# topboard-v2_0.net
KiCad netlist of a schematic drawn in EAGLE
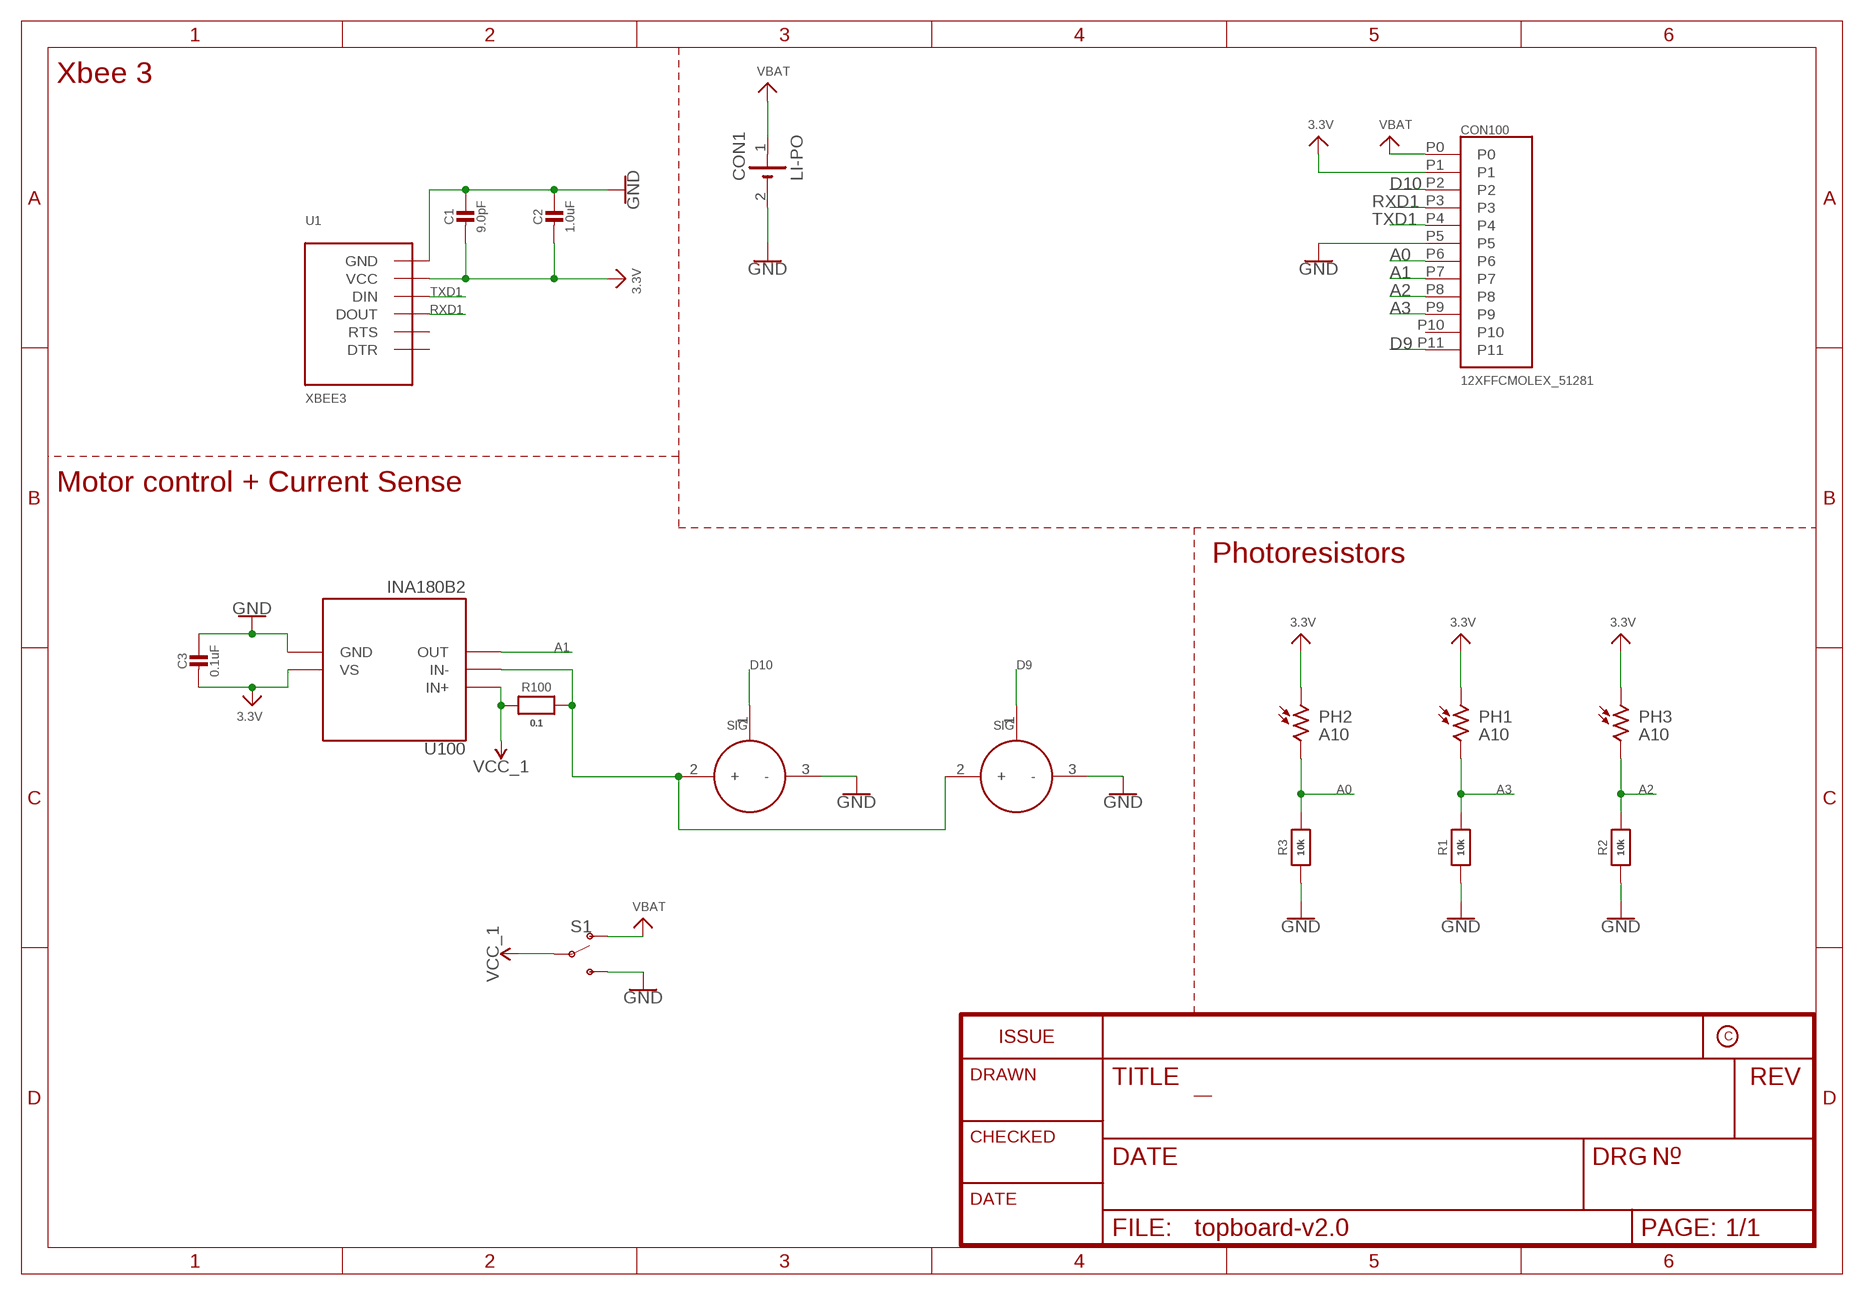
[diagram p0: schematic, sheet 1]

(export (version "E")
  (design (tool "Eeschema 10.0.6"))
  (components
    (comp (ref "C1")
      (value "9.0pF")
      (footprint "eagle-import:_0603MP")
      (libsource (lib "eagle-import") (part "CAP_CERAMIC_0603MP"))
    )
    (comp (ref "C2")
      (value "1.0uF")
      (footprint "eagle-import:_0603MP")
      (libsource (lib "eagle-import") (part "CAP_CERAMIC_0603MP"))
    )
    (comp (ref "C3")
      (value "0.1uF")
      (footprint "eagle-import:_0603MP")
      (libsource (lib "eagle-import") (part "CAP_CERAMIC_0603MP"))
    )
    (comp (ref "CON1")
      (value "LI-PO")
      (footprint "eagle-import:1X02_BATT")
      (libsource (lib "eagle-import") (part "LI-PO"))
    )
    (comp (ref "CON100")
      (value "12XFFCMOLEX_51281")
      (footprint "eagle-import:MOLEX_51281-1294")
      (libsource (lib "eagle-import") (part "12XFFCMOLEX_51281"))
    )
    (comp (ref "M1")
      (value "SERVO")
      (footprint "eagle-import:1X03_SERVO")
      (libsource (lib "eagle-import") (part "SERVO"))
    )
    (comp (ref "M2")
      (value "SERVO")
      (footprint "eagle-import:1X03_SERVO")
      (libsource (lib "eagle-import") (part "SERVO"))
    )
    (comp (ref "PH1")
      (value "A10")
      (footprint "eagle-import:PHOTORESISTOR")
      (libsource (lib "eagle-import") (part "A10"))
    )
    (comp (ref "PH2")
      (value "A10")
      (footprint "eagle-import:PHOTORESISTOR")
      (libsource (lib "eagle-import") (part "A10"))
    )
    (comp (ref "PH3")
      (value "A10")
      (footprint "eagle-import:PHOTORESISTOR")
      (libsource (lib "eagle-import") (part "A10"))
    )
    (comp (ref "R1")
      (value "10k")
      (footprint "eagle-import:_0603MP")
      (libsource (lib "eagle-import") (part "RESISTOR_0603MP"))
    )
    (comp (ref "R2")
      (value "10k")
      (footprint "eagle-import:_0603MP")
      (libsource (lib "eagle-import") (part "RESISTOR_0603MP"))
    )
    (comp (ref "R3")
      (value "10k")
      (footprint "eagle-import:_0603MP")
      (libsource (lib "eagle-import") (part "RESISTOR_0603MP"))
    )
    (comp (ref "R100")
      (value "0.1")
      (footprint "eagle-import:_0603MP")
      (libsource (lib "eagle-import") (part "RESISTOR_0603MP"))
    )
    (comp (ref "S1")
      (value "SWITCH-SPDT-SMD-RIGHT-ANGLE")
      (footprint "eagle-import:SWITCH_SPST_SMD_A")
      (libsource (lib "eagle-import") (part "SWITCH-SPDT-SMD-RIGHT-ANGLE"))
    )
    (comp (ref "U1")
      (value "XBEE3")
      (footprint "eagle-import:XBEE3_MICRO")
      (libsource (lib "eagle-import") (part "XBEE3"))
    )
    (comp (ref "U100")
      (value "INA180B2")
      (footprint "eagle-import:SOT23-5")
      (libsource (lib "eagle-import") (part "INA180B2"))
    )
  )
  (nets
    (net (code "1") (name "/A0") (class "Default")
      (node (ref "CON100") (pin "P6") (pinfunction "P6_P6") (pintype "bidirectional"))
      (node (ref "PH2") (pin "2") (pinfunction "2_2") (pintype "passive"))
      (node (ref "R3") (pin "2") (pinfunction "2_2") (pintype "passive"))
    )
    (net (code "2") (name "/A1") (class "Default")
      (node (ref "CON100") (pin "P7") (pinfunction "P7_P7") (pintype "bidirectional"))
      (node (ref "U100") (pin "4") (pinfunction "OUT_4") (pintype "bidirectional"))
    )
    (net (code "3") (name "/A2") (class "Default")
      (node (ref "CON100") (pin "P8") (pinfunction "P8_P8") (pintype "bidirectional"))
      (node (ref "PH3") (pin "2") (pinfunction "2_2") (pintype "passive"))
      (node (ref "R2") (pin "2") (pinfunction "2_2") (pintype "passive"))
    )
    (net (code "4") (name "/A3") (class "Default")
      (node (ref "CON100") (pin "P9") (pinfunction "P9_P9") (pintype "bidirectional"))
      (node (ref "PH1") (pin "2") (pinfunction "2_2") (pintype "passive"))
      (node (ref "R1") (pin "2") (pinfunction "2_2") (pintype "passive"))
    )
    (net (code "5") (name "/D9") (class "Default")
      (node (ref "CON100") (pin "P11") (pinfunction "P11_P11") (pintype "bidirectional"))
      (node (ref "M1") (pin "1") (pinfunction "SIG_1") (pintype "bidirectional"))
    )
    (net (code "6") (name "/D10") (class "Default")
      (node (ref "CON100") (pin "P2") (pinfunction "P2_P2") (pintype "bidirectional"))
      (node (ref "M2") (pin "1") (pinfunction "SIG_1") (pintype "bidirectional"))
    )
    (net (code "7") (name "/RXD1") (class "Default")
      (node (ref "CON100") (pin "P3") (pinfunction "P3_P3") (pintype "bidirectional"))
      (node (ref "U1") (pin "DOUT/DIO13") (pinfunction "DOUT_DOUT/DIO13") (pintype "bidirectional"))
    )
    (net (code "8") (name "/TXD1") (class "Default")
      (node (ref "CON100") (pin "P4") (pinfunction "P4_P4") (pintype "bidirectional"))
      (node (ref "U1") (pin "DIN/CONFIG/DIO14") (pinfunction "DIN_DIN/CONFIG/DIO14") (pintype "bidirectional"))
    )
    (net (code "9") (name "3.3V") (class "Default")
      (node (ref "C1") (pin "2") (pinfunction "2_2") (pintype "passive"))
      (node (ref "C2") (pin "2") (pinfunction "2_2") (pintype "passive"))
      (node (ref "C3") (pin "2") (pinfunction "2_2") (pintype "passive"))
      (node (ref "CON100") (pin "P1") (pinfunction "P1_P1") (pintype "bidirectional"))
      (node (ref "PH1") (pin "1") (pinfunction "1_1") (pintype "passive"))
      (node (ref "PH2") (pin "1") (pinfunction "1_1") (pintype "passive"))
      (node (ref "PH3") (pin "1") (pinfunction "1_1") (pintype "passive"))
      (node (ref "U1") (pin "VCC") (pinfunction "VCC_VCC") (pintype "bidirectional"))
      (node (ref "U100") (pin "5") (pinfunction "VS_5") (pintype "bidirectional"))
    )
    (net (code "10") (name "GND") (class "Default")
      (node (ref "C1") (pin "1") (pinfunction "1_1") (pintype "passive"))
      (node (ref "C2") (pin "1") (pinfunction "1_1") (pintype "passive"))
      (node (ref "C3") (pin "1") (pinfunction "1_1") (pintype "passive"))
      (node (ref "CON1") (pin "2") (pinfunction "-_2") (pintype "passive"))
      (node (ref "CON100") (pin "P5") (pinfunction "P5_P5") (pintype "bidirectional"))
      (node (ref "M1") (pin "3") (pinfunction "-_3") (pintype "bidirectional"))
      (node (ref "M2") (pin "3") (pinfunction "-_3") (pintype "bidirectional"))
      (node (ref "R1") (pin "1") (pinfunction "1_1") (pintype "passive"))
      (node (ref "R2") (pin "1") (pinfunction "1_1") (pintype "passive"))
      (node (ref "R3") (pin "1") (pinfunction "1_1") (pintype "passive"))
      (node (ref "S1") (pin "3") (pinfunction "S_3") (pintype "passive"))
      (node (ref "U1") (pin "GND1") (pinfunction "GND_GND1") (pintype "bidirectional"))
      (node (ref "U1") (pin "GND2") (pinfunction "GND_GND2") (pintype "bidirectional"))
      (node (ref "U1") (pin "GND3") (pinfunction "GND_GND3") (pintype "bidirectional"))
      (node (ref "U1") (pin "GND4") (pinfunction "GND_GND4") (pintype "bidirectional"))
      (node (ref "U1") (pin "GND5") (pinfunction "GND_GND5") (pintype "bidirectional"))
      (node (ref "U1") (pin "GND6") (pinfunction "GND_GND6") (pintype "bidirectional"))
      (node (ref "U100") (pin "2") (pinfunction "GND_2") (pintype "bidirectional"))
    )
    (net (code "11") (name "Net-(M1-+)") (class "Default")
      (node (ref "M1") (pin "2") (pinfunction "+_2") (pintype "bidirectional"))
      (node (ref "M2") (pin "2") (pinfunction "+_2") (pintype "bidirectional"))
      (node (ref "R100") (pin "2") (pinfunction "2_2") (pintype "passive"))
      (node (ref "U100") (pin "3") (pinfunction "IN-_3") (pintype "bidirectional"))
    )
    (net (code "12") (name "VBAT") (class "Default")
      (node (ref "CON1") (pin "1") (pinfunction "+_1") (pintype "passive"))
      (node (ref "CON100") (pin "P0") (pinfunction "P0_P0") (pintype "bidirectional"))
      (node (ref "S1") (pin "1") (pinfunction "O_1") (pintype "passive"))
    )
    (net (code "13") (name "VCC_1") (class "Default")
      (node (ref "R100") (pin "1") (pinfunction "1_1") (pintype "passive"))
      (node (ref "S1") (pin "2") (pinfunction "P_2") (pintype "passive"))
      (node (ref "U100") (pin "1") (pinfunction "IN+_1") (pintype "bidirectional"))
    )
    (net (code "14") (name "unconnected-(CON100-PadP10)") (class "Default")
      (node (ref "CON100") (pin "P10") (pinfunction "P10_P10") (pintype "bidirectional"))
    )
    (net (code "15") (name "unconnected-(U1-DTR-PadDTR{slash}SLEEP_RQ{slash}DIO8)") (class "Default")
      (node (ref "U1") (pin "DTR/SLEEP_RQ/DIO8") (pinfunction "DTR_DTR/SLEEP_RQ/DIO8") (pintype "bidirectional"))
    )
    (net (code "16") (name "unconnected-(U1-RTS-PadRTS{slash}DIO6)") (class "Default")
      (node (ref "U1") (pin "RTS/DIO6") (pinfunction "RTS_RTS/DIO6") (pintype "bidirectional"))
    )
  )
)
